# DAC.net
KiCad netlist of a schematic drawn in Altium Designer
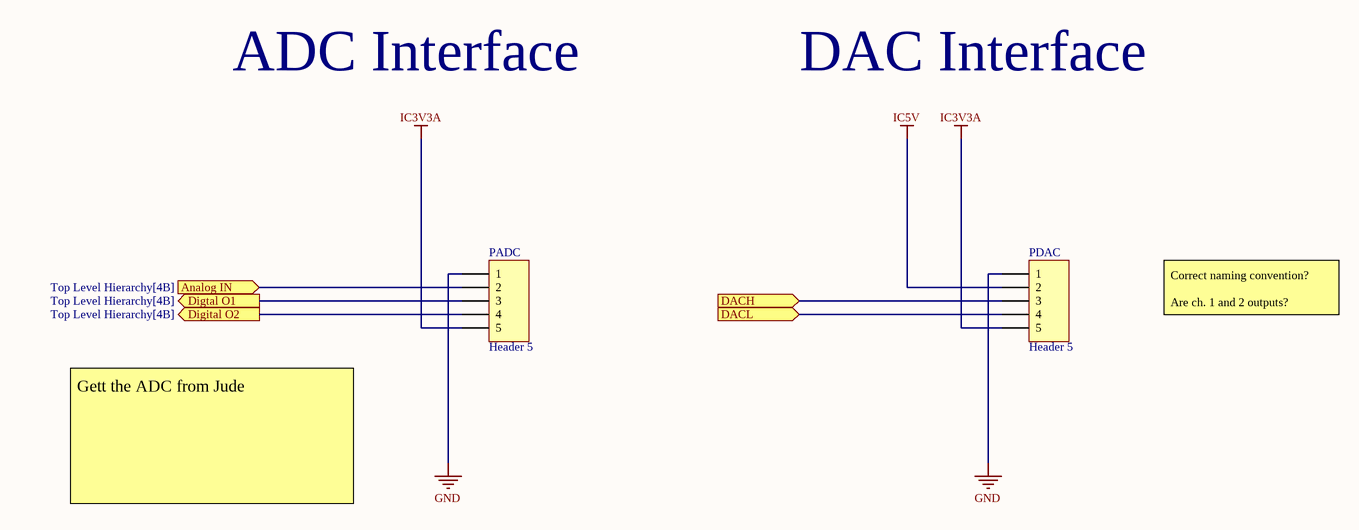
[diagram p0: DAC.SchDoc]

(export (version "E")
  (design (tool "Eeschema 10.0.6"))
  (components
    (comp (ref "PADC")
      (value "Header 5")
      (footprint "HDR1X5")
      (description "Header, 5-Pin Male")
      (fields (field (name "MPN") "PEC05SFAN"))
      (libsource (lib "esd_library") (part "Header 5"))
    )
    (comp (ref "PDAC")
      (value "Header 5")
      (footprint "HDR1X5")
      (description "Header, 5-Pin Male")
      (fields (field (name "MPN") "PEC05SFAN"))
      (libsource (lib "esd_library") (part "Header 5"))
    )
  )
  (nets
    (net (code "1") (name "/Analog IN") (class "Default")
      (node (ref "PADC") (pin "2") (pinfunction "2_2") (pintype "passive"))
    )
    (net (code "2") (name "/DACH") (class "Default")
      (node (ref "PDAC") (pin "3") (pinfunction "3_3") (pintype "passive"))
    )
    (net (code "3") (name "/DACL") (class "Default")
      (node (ref "PDAC") (pin "4") (pinfunction "4_4") (pintype "passive"))
    )
    (net (code "4") (name "/Digital O2") (class "Default")
      (node (ref "PADC") (pin "4") (pinfunction "4_4") (pintype "passive"))
    )
    (net (code "5") (name "/Digtal O1") (class "Default")
      (node (ref "PADC") (pin "3") (pinfunction "3_3") (pintype "passive"))
    )
    (net (code "6") (name "GND") (class "Default")
      (node (ref "PADC") (pin "1") (pinfunction "1_1") (pintype "passive"))
      (node (ref "PDAC") (pin "1") (pinfunction "1_1") (pintype "passive"))
    )
    (net (code "7") (name "IC3V3A") (class "Default")
      (node (ref "PADC") (pin "5") (pinfunction "5_5") (pintype "passive"))
      (node (ref "PDAC") (pin "5") (pinfunction "5_5") (pintype "passive"))
    )
    (net (code "8") (name "IC5V") (class "Default")
      (node (ref "PDAC") (pin "2") (pinfunction "2_2") (pintype "passive"))
    )
  )
)
